# particle-logo-v1.net
KiCad netlist of a schematic drawn in EAGLE
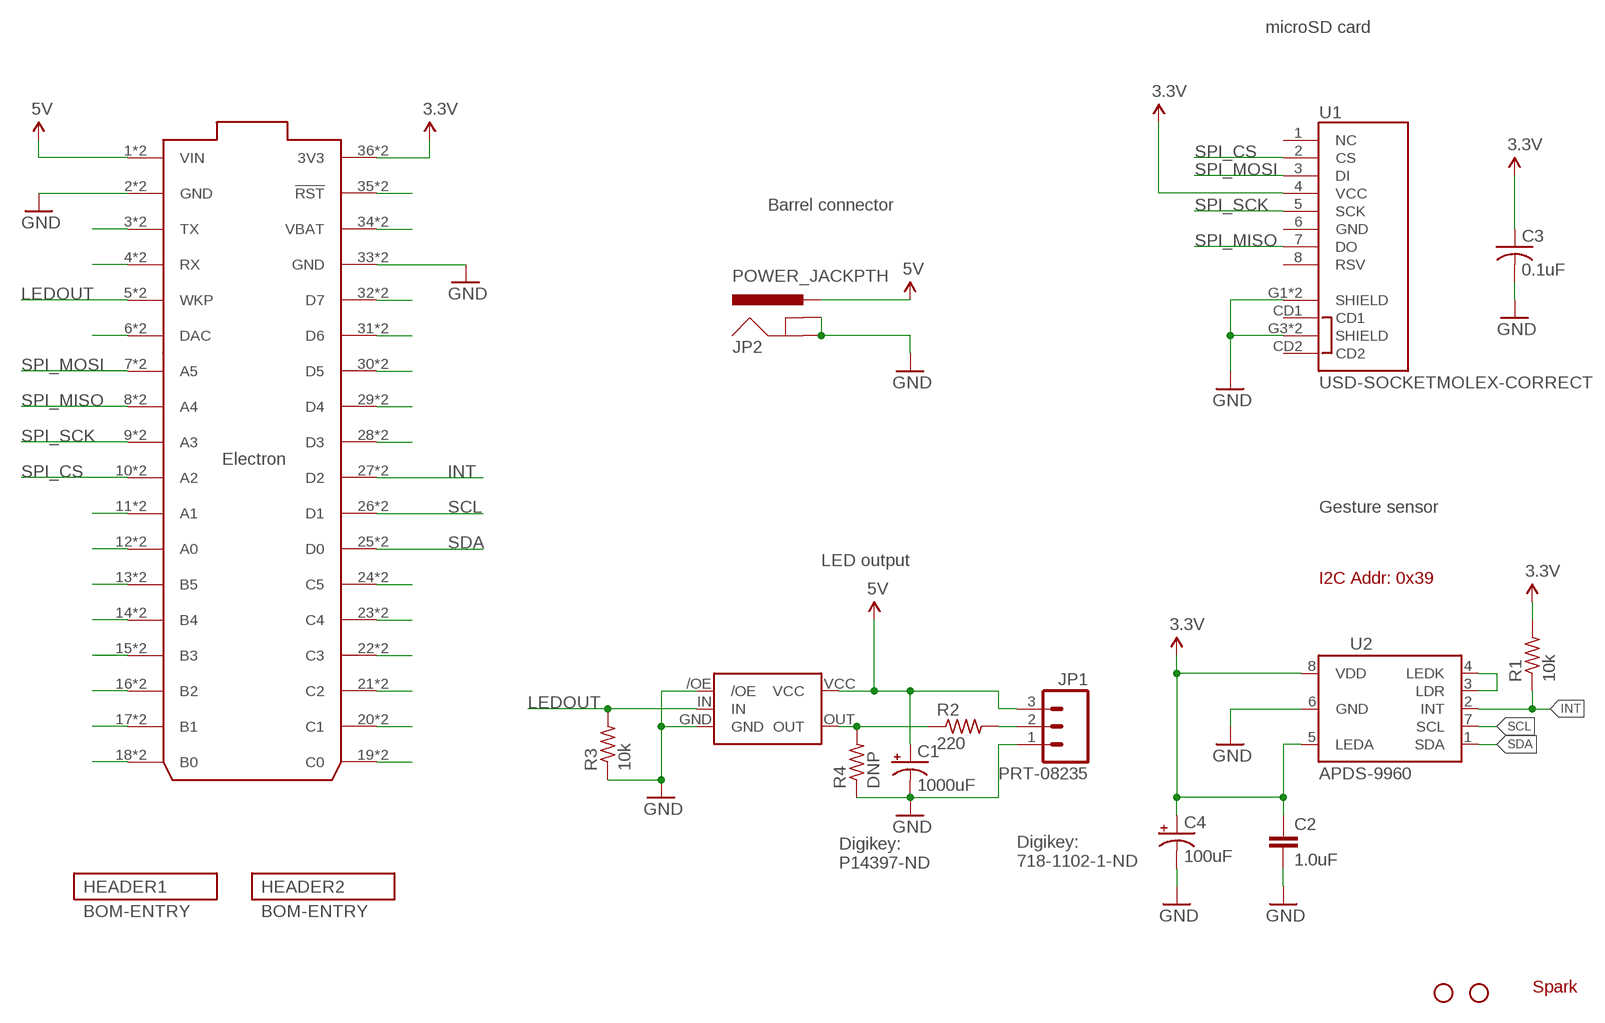
[diagram p0: schematic, sheet 1]

(export (version "E")
  (design (tool "Eeschema 10.0.6"))
  (components
    (comp (ref "C1")
      (value "1000uF")
      (footprint "eagle-import:CPOL-8MMX20MM-FLAT-MIR")
      (fields (field (name "PARTNO") "EEU-FR1C102L"))
      (libsource (lib "eagle-import") (part "CAP_POL8MMX20MM-FLAT-MIR"))
    )
    (comp (ref "C2")
      (value "1.0uF")
      (footprint "eagle-import:0603-CAP")
      (fields (field (name "PARTNO") "0603YD105KAT2A"))
      (libsource (lib "eagle-import") (part "1.0UF-16V-10%(0603)"))
    )
    (comp (ref "C3")
      (value "0.1uF")
      (footprint "eagle-import:C0603")
      (fields (field (name "PARTNO") "CC0603JRX7R7BB104"))
      (libsource (lib "eagle-import") (part "C-USC0603"))
    )
    (comp (ref "C4")
      (value "100uF")
      (footprint "eagle-import:EIA7343")
      (fields (field (name "PARTNO") "TAJD107K020RNJ"))
      (libsource (lib "eagle-import") (part "100UF-10V-10%(TANT)"))
    )
    (comp (ref "JP1")
      (value "PRT-08235")
      (footprint "eagle-import:SCREWTERMINAL-3.5MM-3")
      (libsource (lib "eagle-import") (part "M03SCREW"))
    )
    (comp (ref "JP2")
      (value "POWER_JACKPTH")
      (footprint "eagle-import:POWER_JACK_PTH")
      (libsource (lib "eagle-import") (part "POWER_JACKPTH"))
    )
    (comp (ref "R1")
      (value "10k")
      (footprint "eagle-import:R0603")
      (fields (field (name "PARTNO") "ERJ-3EKF1002V"))
      (libsource (lib "eagle-import") (part "R-US_R0603"))
    )
    (comp (ref "R2")
      (value "220")
      (footprint "eagle-import:R0603")
      (fields (field (name "PARTNO") "ERJ-3GEYJ221V"))
      (libsource (lib "eagle-import") (part "R-US_R0603"))
    )
    (comp (ref "R3")
      (value "10k")
      (footprint "eagle-import:R0603")
      (fields (field (name "PARTNO") "ERJ-3EKF1002V"))
      (libsource (lib "eagle-import") (part "R-US_R0603"))
    )
    (comp (ref "R4")
      (value "DNP")
      (footprint "eagle-import:R0603")
      (libsource (lib "eagle-import") (part "R-US_R0603"))
    )
    (comp (ref "STANDOFF1")
      (value "STAND-OFFSCREW-2")
      (footprint "eagle-import:STAND-OFF-2")
      (libsource (lib "eagle-import") (part "STAND-OFFSCREW-2"))
    )
    (comp (ref "STANDOFF2")
      (value "STAND-OFFSCREW-2")
      (footprint "eagle-import:STAND-OFF-2")
      (libsource (lib "eagle-import") (part "STAND-OFFSCREW-2"))
    )
    (comp (ref "U$1")
      (value "SPARK_LOGO2")
      (footprint "eagle-import:SPARK_LOGO2")
      (libsource (lib "eagle-import") (part "SPARK_LOGO2"))
    )
    (comp (ref "U1")
      (value "USD-SOCKETMOLEX-CORRECT")
      (footprint "eagle-import:MICRO-SD-MOLEX-CORRECT")
      (fields (field (name "PARTNO") "1040310811"))
      (libsource (lib "eagle-import") (part "USD-SOCKETMOLEX-CORRECT"))
    )
    (comp (ref "U2")
      (value "APDS-9960")
      (footprint "eagle-import:APDS-9960")
      (libsource (lib "eagle-import") (part "APDS-9960"))
    )
    (comp (ref "U3")
      (value "ELECTRON_WITH_EXTERNAL_HEADERS_NT")
      (footprint "eagle-import:ELECTRON_EXTERNAL_NT")
      (libsource (lib "eagle-import") (part "ELECTRON_WITH_EXTERNAL_HEADERS_NT"))
    )
    (comp (ref "U4")
      (value "NL17SZ125SOT553")
      (footprint "eagle-import:SOT-553")
      (fields (field (name "PARTNO") "NL17SZ125DTT1G"))
      (libsource (lib "eagle-import") (part "NL17SZ125SOT553"))
    )
  )
  (nets
    (net (code "1") (name "/LEDOUT") (class "Default")
      (node (ref "R3") (pin "2") (pinfunction "2_2") (pintype "passive"))
      (node (ref "U3") (pin "5") (pinfunction "WKP_5") (pintype "bidirectional"))
      (node (ref "U3") (pin "@5") (pinfunction "WKP_@5") (pintype "bidirectional"))
      (node (ref "U4") (pin "IN") (pinfunction "IN_IN") (pintype "bidirectional"))
    )
    (net (code "2") (name "/SPI_CS") (class "Default")
      (node (ref "U1") (pin "2") (pinfunction "CS_2") (pintype "bidirectional"))
      (node (ref "U3") (pin "10") (pinfunction "A2_10") (pintype "bidirectional"))
      (node (ref "U3") (pin "@10") (pinfunction "A2_@10") (pintype "bidirectional"))
    )
    (net (code "3") (name "/SPI_MISO") (class "Default")
      (node (ref "U1") (pin "7") (pinfunction "DO_7") (pintype "bidirectional"))
      (node (ref "U3") (pin "8") (pinfunction "A4_8") (pintype "bidirectional"))
      (node (ref "U3") (pin "@8") (pinfunction "A4_@8") (pintype "bidirectional"))
    )
    (net (code "4") (name "/SPI_MOSI") (class "Default")
      (node (ref "U1") (pin "3") (pinfunction "DI_3") (pintype "bidirectional"))
      (node (ref "U3") (pin "7") (pinfunction "A5_7") (pintype "bidirectional"))
      (node (ref "U3") (pin "@7") (pinfunction "A5_@7") (pintype "bidirectional"))
    )
    (net (code "5") (name "/SPI_SCK") (class "Default")
      (node (ref "U1") (pin "5") (pinfunction "SCK_5") (pintype "bidirectional"))
      (node (ref "U3") (pin "9") (pinfunction "A3_9") (pintype "bidirectional"))
      (node (ref "U3") (pin "@9") (pinfunction "A3_@9") (pintype "bidirectional"))
    )
    (net (code "6") (name "3.3V") (class "Default")
      (node (ref "C2") (pin "1") (pinfunction "1_1") (pintype "passive"))
      (node (ref "C3") (pin "1") (pinfunction "1_1") (pintype "passive"))
      (node (ref "C4") (pin "A") (pinfunction "+_A") (pintype "passive"))
      (node (ref "R1") (pin "2") (pinfunction "2_2") (pintype "passive"))
      (node (ref "U1") (pin "4") (pinfunction "VCC_4") (pintype "bidirectional"))
      (node (ref "U2") (pin "5") (pinfunction "LEDA_5") (pintype "bidirectional"))
      (node (ref "U2") (pin "8") (pinfunction "VDD_8") (pintype "bidirectional"))
      (node (ref "U3") (pin "36") (pinfunction "3V3_36") (pintype "power_in"))
      (node (ref "U3") (pin "@36") (pinfunction "3V3_@36") (pintype "power_in"))
    )
    (net (code "7") (name "5V") (class "Default")
      (node (ref "C1") (pin "2") (pinfunction "+_2") (pintype "passive"))
      (node (ref "JP1") (pin "3") (pinfunction "3_3") (pintype "passive"))
      (node (ref "JP2") (pin "PWR") (pinfunction "PWR_PWR") (pintype "bidirectional"))
      (node (ref "U3") (pin "1") (pinfunction "VIN_1") (pintype "power_in"))
      (node (ref "U3") (pin "@1") (pinfunction "VIN_@1") (pintype "power_in"))
      (node (ref "U4") (pin "VCC") (pinfunction "VCC_VCC") (pintype "bidirectional"))
    )
    (net (code "8") (name "GND") (class "Default")
      (node (ref "C1") (pin "1") (pinfunction "-_1") (pintype "passive"))
      (node (ref "C2") (pin "2") (pinfunction "2_2") (pintype "passive"))
      (node (ref "C3") (pin "2") (pinfunction "2_2") (pintype "passive"))
      (node (ref "C4") (pin "C") (pinfunction "-_C") (pintype "passive"))
      (node (ref "JP1") (pin "1") (pinfunction "1_1") (pintype "passive"))
      (node (ref "JP2") (pin "GND") (pinfunction "GND_GND") (pintype "bidirectional"))
      (node (ref "JP2") (pin "GNDBREAK") (pinfunction "GNDBREAK_GNDBREAK") (pintype "bidirectional"))
      (node (ref "R3") (pin "1") (pinfunction "1_1") (pintype "passive"))
      (node (ref "R4") (pin "1") (pinfunction "1_1") (pintype "passive"))
      (node (ref "U1") (pin "G1") (pinfunction "SHIELD_G1") (pintype "bidirectional"))
      (node (ref "U1") (pin "G2") (pinfunction "SHIELD_G2") (pintype "bidirectional"))
      (node (ref "U1") (pin "G3") (pinfunction "SHIELD_G3") (pintype "bidirectional"))
      (node (ref "U1") (pin "G4") (pinfunction "SHIELD_G4") (pintype "bidirectional"))
      (node (ref "U2") (pin "6") (pinfunction "GND_6") (pintype "bidirectional"))
      (node (ref "U3") (pin "2") (pinfunction "GND_2") (pintype "power_in"))
      (node (ref "U3") (pin "33") (pinfunction "GND_33") (pintype "power_in"))
      (node (ref "U3") (pin "@2") (pinfunction "GND_@2") (pintype "power_in"))
      (node (ref "U3") (pin "@33") (pinfunction "GND_@33") (pintype "power_in"))
      (node (ref "U4") (pin "/OE") (pinfunction "/OE_/OE") (pintype "bidirectional"))
      (node (ref "U4") (pin "GND") (pinfunction "GND_GND") (pintype "bidirectional"))
    )
    (net (code "9") (name "INT") (class "Default")
      (node (ref "R1") (pin "1") (pinfunction "1_1") (pintype "passive"))
      (node (ref "U2") (pin "2") (pinfunction "INT_2") (pintype "bidirectional"))
      (node (ref "U3") (pin "27") (pinfunction "D2_27") (pintype "bidirectional"))
      (node (ref "U3") (pin "@27") (pinfunction "D2_@27") (pintype "bidirectional"))
    )
    (net (code "10") (name "Net-(JP1-Pad2)") (class "Default")
      (node (ref "JP1") (pin "2") (pinfunction "2_2") (pintype "passive"))
      (node (ref "R2") (pin "2") (pinfunction "2_2") (pintype "passive"))
    )
    (net (code "11") (name "Net-(R2-Pad1)") (class "Default")
      (node (ref "R2") (pin "1") (pinfunction "1_1") (pintype "passive"))
      (node (ref "R4") (pin "2") (pinfunction "2_2") (pintype "passive"))
      (node (ref "U4") (pin "OUT") (pinfunction "OUT_OUT") (pintype "bidirectional"))
    )
    (net (code "12") (name "Net-(U2-LDR)") (class "Default")
      (node (ref "U2") (pin "3") (pinfunction "LDR_3") (pintype "bidirectional"))
      (node (ref "U2") (pin "4") (pinfunction "LEDK_4") (pintype "bidirectional"))
    )
    (net (code "13") (name "Net-(U3-A0-Pad12)") (class "Default")
      (node (ref "U3") (pin "12") (pinfunction "A0_12") (pintype "bidirectional"))
      (node (ref "U3") (pin "@12") (pinfunction "A0_@12") (pintype "bidirectional"))
    )
    (net (code "14") (name "Net-(U3-A1-Pad11)") (class "Default")
      (node (ref "U3") (pin "11") (pinfunction "A1_11") (pintype "bidirectional"))
      (node (ref "U3") (pin "@11") (pinfunction "A1_@11") (pintype "bidirectional"))
    )
    (net (code "15") (name "Net-(U3-B0-Pad18)") (class "Default")
      (node (ref "U3") (pin "18") (pinfunction "B0_18") (pintype "bidirectional"))
      (node (ref "U3") (pin "@18") (pinfunction "B0_@18") (pintype "bidirectional"))
    )
    (net (code "16") (name "Net-(U3-B1-Pad17)") (class "Default")
      (node (ref "U3") (pin "17") (pinfunction "B1_17") (pintype "bidirectional"))
      (node (ref "U3") (pin "@17") (pinfunction "B1_@17") (pintype "bidirectional"))
    )
    (net (code "17") (name "Net-(U3-B2-Pad16)") (class "Default")
      (node (ref "U3") (pin "16") (pinfunction "B2_16") (pintype "bidirectional"))
      (node (ref "U3") (pin "@16") (pinfunction "B2_@16") (pintype "bidirectional"))
    )
    (net (code "18") (name "Net-(U3-B3-Pad15)") (class "Default")
      (node (ref "U3") (pin "15") (pinfunction "B3_15") (pintype "bidirectional"))
      (node (ref "U3") (pin "@15") (pinfunction "B3_@15") (pintype "bidirectional"))
    )
    (net (code "19") (name "Net-(U3-B4-Pad14)") (class "Default")
      (node (ref "U3") (pin "14") (pinfunction "B4_14") (pintype "bidirectional"))
      (node (ref "U3") (pin "@14") (pinfunction "B4_@14") (pintype "bidirectional"))
    )
    (net (code "20") (name "Net-(U3-B5-Pad13)") (class "Default")
      (node (ref "U3") (pin "13") (pinfunction "B5_13") (pintype "bidirectional"))
      (node (ref "U3") (pin "@13") (pinfunction "B5_@13") (pintype "bidirectional"))
    )
    (net (code "21") (name "Net-(U3-C0-Pad19)") (class "Default")
      (node (ref "U3") (pin "19") (pinfunction "C0_19") (pintype "bidirectional"))
      (node (ref "U3") (pin "@19") (pinfunction "C0_@19") (pintype "bidirectional"))
    )
    (net (code "22") (name "Net-(U3-C1-Pad20)") (class "Default")
      (node (ref "U3") (pin "20") (pinfunction "C1_20") (pintype "bidirectional"))
      (node (ref "U3") (pin "@20") (pinfunction "C1_@20") (pintype "bidirectional"))
    )
    (net (code "23") (name "Net-(U3-C2-Pad21)") (class "Default")
      (node (ref "U3") (pin "21") (pinfunction "C2_21") (pintype "bidirectional"))
      (node (ref "U3") (pin "@21") (pinfunction "C2_@21") (pintype "bidirectional"))
    )
    (net (code "24") (name "Net-(U3-C3-Pad22)") (class "Default")
      (node (ref "U3") (pin "22") (pinfunction "C3_22") (pintype "bidirectional"))
      (node (ref "U3") (pin "@22") (pinfunction "C3_@22") (pintype "bidirectional"))
    )
    (net (code "25") (name "Net-(U3-C4-Pad23)") (class "Default")
      (node (ref "U3") (pin "23") (pinfunction "C4_23") (pintype "bidirectional"))
      (node (ref "U3") (pin "@23") (pinfunction "C4_@23") (pintype "bidirectional"))
    )
    (net (code "26") (name "Net-(U3-C5-Pad24)") (class "Default")
      (node (ref "U3") (pin "24") (pinfunction "C5_24") (pintype "bidirectional"))
      (node (ref "U3") (pin "@24") (pinfunction "C5_@24") (pintype "bidirectional"))
    )
    (net (code "27") (name "Net-(U3-D3-Pad28)") (class "Default")
      (node (ref "U3") (pin "28") (pinfunction "D3_28") (pintype "bidirectional"))
      (node (ref "U3") (pin "@28") (pinfunction "D3_@28") (pintype "bidirectional"))
    )
    (net (code "28") (name "Net-(U3-D4-Pad29)") (class "Default")
      (node (ref "U3") (pin "29") (pinfunction "D4_29") (pintype "bidirectional"))
      (node (ref "U3") (pin "@29") (pinfunction "D4_@29") (pintype "bidirectional"))
    )
    (net (code "29") (name "Net-(U3-D5-Pad30)") (class "Default")
      (node (ref "U3") (pin "30") (pinfunction "D5_30") (pintype "bidirectional"))
      (node (ref "U3") (pin "@30") (pinfunction "D5_@30") (pintype "bidirectional"))
    )
    (net (code "30") (name "Net-(U3-D6-Pad31)") (class "Default")
      (node (ref "U3") (pin "31") (pinfunction "D6_31") (pintype "bidirectional"))
      (node (ref "U3") (pin "@31") (pinfunction "D6_@31") (pintype "bidirectional"))
    )
    (net (code "31") (name "Net-(U3-D7-Pad32)") (class "Default")
      (node (ref "U3") (pin "32") (pinfunction "D7_32") (pintype "bidirectional"))
      (node (ref "U3") (pin "@32") (pinfunction "D7_@32") (pintype "bidirectional"))
    )
    (net (code "32") (name "Net-(U3-DAC-Pad6)") (class "Default")
      (node (ref "U3") (pin "6") (pinfunction "DAC_6") (pintype "bidirectional"))
      (node (ref "U3") (pin "@6") (pinfunction "DAC_@6") (pintype "bidirectional"))
    )
    (net (code "33") (name "Net-(U3-RX-Pad4)") (class "Default")
      (node (ref "U3") (pin "4") (pinfunction "RX_4") (pintype "bidirectional"))
      (node (ref "U3") (pin "@4") (pinfunction "RX_@4") (pintype "bidirectional"))
    )
    (net (code "34") (name "Net-(U3-TX-Pad3)") (class "Default")
      (node (ref "U3") (pin "3") (pinfunction "TX_3") (pintype "bidirectional"))
      (node (ref "U3") (pin "@3") (pinfunction "TX_@3") (pintype "bidirectional"))
    )
    (net (code "35") (name "Net-(U3-VBAT-Pad34)") (class "Default")
      (node (ref "U3") (pin "34") (pinfunction "VBAT_34") (pintype "power_in"))
      (node (ref "U3") (pin "@34") (pinfunction "VBAT_@34") (pintype "power_in"))
    )
    (net (code "36") (name "Net-(U3-~{RST}-Pad35)") (class "Default")
      (node (ref "U3") (pin "35") (pinfunction "~{RST}_35") (pintype "bidirectional"))
      (node (ref "U3") (pin "@35") (pinfunction "~{RST}_@35") (pintype "bidirectional"))
    )
    (net (code "37") (name "SCL") (class "Default")
      (node (ref "U2") (pin "7") (pinfunction "SCL_7") (pintype "bidirectional"))
      (node (ref "U3") (pin "26") (pinfunction "D1_26") (pintype "bidirectional"))
      (node (ref "U3") (pin "@26") (pinfunction "D1_@26") (pintype "bidirectional"))
    )
    (net (code "38") (name "SDA") (class "Default")
      (node (ref "U2") (pin "1") (pinfunction "SDA_1") (pintype "bidirectional"))
      (node (ref "U3") (pin "25") (pinfunction "D0_25") (pintype "bidirectional"))
      (node (ref "U3") (pin "@25") (pinfunction "D0_@25") (pintype "bidirectional"))
    )
    (net (code "39") (name "unconnected-(U1-GND-Pad6)") (class "Default")
      (node (ref "U1") (pin "6") (pinfunction "GND_6") (pintype "bidirectional"))
    )
    (net (code "40") (name "unconnected-(U1-NC-Pad1)") (class "Default")
      (node (ref "U1") (pin "1") (pinfunction "NC_1") (pintype "bidirectional"))
    )
    (net (code "41") (name "unconnected-(U1-PadCD1)") (class "Default")
      (node (ref "U1") (pin "CD1") (pinfunction "CD1_CD1") (pintype "bidirectional"))
    )
    (net (code "42") (name "unconnected-(U1-PadCD2)") (class "Default")
      (node (ref "U1") (pin "CD2") (pinfunction "CD2_CD2") (pintype "bidirectional"))
    )
    (net (code "43") (name "unconnected-(U1-RSV-Pad8)") (class "Default")
      (node (ref "U1") (pin "8") (pinfunction "RSV_8") (pintype "bidirectional"))
    )
  )
)
